# anemometer_v4.net
KiCad netlist of a schematic drawn in EAGLE
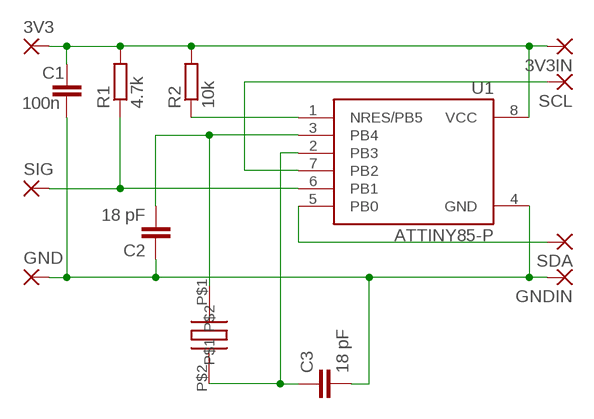
[diagram p0: schematic, sheet 1]

(export (version "E")
  (design (tool "Eeschema 10.0.6"))
  (components
    (comp (ref "3V3")
      (value "1,6/0,9")
      (footprint "eagle-import:1,6_0,9")
      (libsource (lib "eagle-import") (part "1,6/0,9"))
    )
    (comp (ref "3V3IN")
      (value "1,6/0,9")
      (footprint "eagle-import:1,6_0,9")
      (libsource (lib "eagle-import") (part "1,6/0,9"))
    )
    (comp (ref "C1")
      (value "100n")
      (footprint "eagle-import:C1206")
      (libsource (lib "eagle-import") (part "C-EUC1206"))
    )
    (comp (ref "C2")
      (value "18 pF")
      (footprint "eagle-import:C0805")
      (libsource (lib "eagle-import") (part "C-EUC0805"))
    )
    (comp (ref "C3")
      (value "18 pF")
      (footprint "eagle-import:C0805")
      (libsource (lib "eagle-import") (part "C-EUC0805"))
    )
    (comp (ref "GND")
      (value "1,6/0,9")
      (footprint "eagle-import:1,6_0,9")
      (libsource (lib "eagle-import") (part "1,6/0,9"))
    )
    (comp (ref "GNDIN")
      (value "1,6/0,9")
      (footprint "eagle-import:1,6_0,9")
      (libsource (lib "eagle-import") (part "1,6/0,9"))
    )
    (comp (ref "R1")
      (value "4.7k")
      (footprint "eagle-import:R1206")
      (libsource (lib "eagle-import") (part "R-EU_R1206"))
    )
    (comp (ref "R2")
      (value "10k")
      (footprint "eagle-import:R0805")
      (libsource (lib "eagle-import") (part "R-EU_R0805"))
    )
    (comp (ref "SCL")
      (value "1,6/0,9")
      (footprint "eagle-import:1,6_0,9")
      (libsource (lib "eagle-import") (part "1,6/0,9"))
    )
    (comp (ref "SDA")
      (value "1,6/0,9")
      (footprint "eagle-import:1,6_0,9")
      (libsource (lib "eagle-import") (part "1,6/0,9"))
    )
    (comp (ref "SIG")
      (value "1,6/0,9")
      (footprint "eagle-import:1,6_0,9")
      (libsource (lib "eagle-import") (part "1,6/0,9"))
    )
    (comp (ref "U$1")
      (value "QCL16.0000F18B23B")
      (footprint "eagle-import:QCL16.0000F18B23B")
      (libsource (lib "eagle-import") (part "QCL16.0000F18B23B"))
    )
    (comp (ref "U1")
      (value "ATTINY85-P")
      (footprint "eagle-import:PDIP08_300MIL")
      (libsource (lib "eagle-import") (part "ATTINY85P-"))
    )
  )
  (nets
    (net (code "1") (name "Net-(3V3-P)") (class "Default")
      (node (ref "3V3") (pin "1") (pinfunction "P_1") (pintype "passive"))
      (node (ref "3V3IN") (pin "1") (pinfunction "P_1") (pintype "passive"))
      (node (ref "C1") (pin "1") (pinfunction "1_1") (pintype "passive"))
      (node (ref "R1") (pin "2") (pinfunction "2_2") (pintype "passive"))
      (node (ref "R2") (pin "2") (pinfunction "2_2") (pintype "passive"))
      (node (ref "U1") (pin "8") (pinfunction "VCC_8") (pintype "power_in"))
    )
    (net (code "2") (name "Net-(GND-P)") (class "Default")
      (node (ref "C1") (pin "2") (pinfunction "2_2") (pintype "passive"))
      (node (ref "C2") (pin "1") (pinfunction "1_1") (pintype "passive"))
      (node (ref "C3") (pin "2") (pinfunction "2_2") (pintype "passive"))
      (node (ref "GND") (pin "1") (pinfunction "P_1") (pintype "passive"))
      (node (ref "GNDIN") (pin "1") (pinfunction "P_1") (pintype "passive"))
      (node (ref "U1") (pin "4") (pinfunction "GND_4") (pintype "power_in"))
    )
    (net (code "3") (name "Net-(SCL-P)") (class "Default")
      (node (ref "SCL") (pin "1") (pinfunction "P_1") (pintype "passive"))
      (node (ref "U1") (pin "7") (pinfunction "PB2_7") (pintype "bidirectional"))
    )
    (net (code "4") (name "Net-(SDA-P)") (class "Default")
      (node (ref "SDA") (pin "1") (pinfunction "P_1") (pintype "passive"))
      (node (ref "U1") (pin "5") (pinfunction "PB0_5") (pintype "bidirectional"))
    )
    (net (code "5") (name "Net-(SIG-P)") (class "Default")
      (node (ref "R1") (pin "1") (pinfunction "1_1") (pintype "passive"))
      (node (ref "SIG") (pin "1") (pinfunction "P_1") (pintype "passive"))
      (node (ref "U1") (pin "6") (pinfunction "PB1_6") (pintype "bidirectional"))
    )
    (net (code "6") (name "Net-(U1-NRES{slash}PB5)") (class "Default")
      (node (ref "R2") (pin "1") (pinfunction "1_1") (pintype "passive"))
      (node (ref "U1") (pin "1") (pinfunction "NRES/PB5_1") (pintype "bidirectional"))
    )
    (net (code "7") (name "Net-(U1-PB3)") (class "Default")
      (node (ref "C3") (pin "1") (pinfunction "1_1") (pintype "passive"))
      (node (ref "U$1") (pin "P$2") (pinfunction "P$2_P$2") (pintype "bidirectional"))
      (node (ref "U1") (pin "2") (pinfunction "PB3_2") (pintype "bidirectional"))
    )
    (net (code "8") (name "Net-(U1-PB4)") (class "Default")
      (node (ref "C2") (pin "2") (pinfunction "2_2") (pintype "passive"))
      (node (ref "U$1") (pin "P$1") (pinfunction "P$1_P$1") (pintype "bidirectional"))
      (node (ref "U1") (pin "3") (pinfunction "PB4_3") (pintype "bidirectional"))
    )
  )
)
